# CaRe_Schematic_SMD_TOP_PANEL.net
KiCad netlist of a schematic drawn in Altium Designer
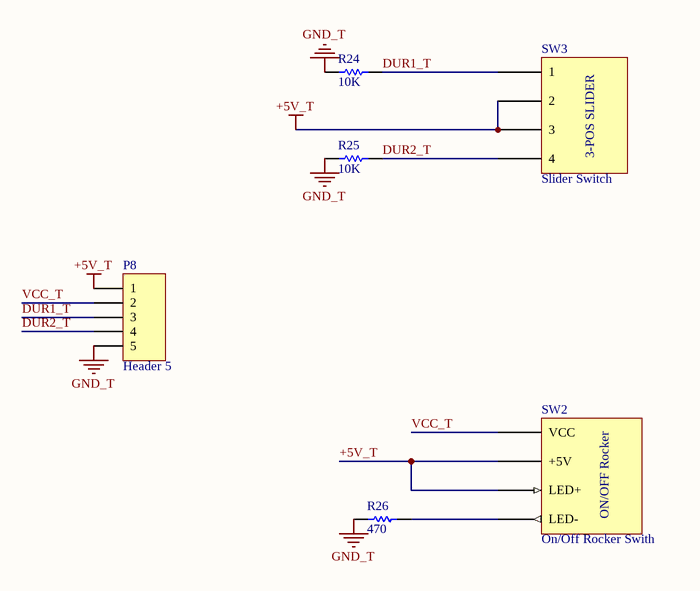
[diagram p0: CaRe_Schematic_SMD_TOP_PANEL.SchDoc]

(export (version "E")
  (design (tool "Eeschema 10.0.6"))
  (components
    (comp (ref "P8")
      (value "Header 5")
      (footprint "HDR1X5")
      (description "Header, 5-Pin")
      (fields (field (name "PUBLISHER") "Altium Limited"))
      (libsource (lib "CaRe_SchematicLib") (part "Header 5"))
    )
    (comp (ref "R24")
      (value "10K")
      (footprint "RES0805")
      (description "Resistor")
      (fields (field (name "PUBLISHER") "Altium Limited"))
      (libsource (lib "CaRe_SchematicLib") (part "Chip Res"))
    )
    (comp (ref "R25")
      (value "10K")
      (footprint "RES0805")
      (description "Resistor")
      (fields (field (name "PUBLISHER") "Altium Limited"))
      (libsource (lib "CaRe_SchematicLib") (part "Chip Res"))
    )
    (comp (ref "R26")
      (value "470")
      (footprint "RES0805")
      (description "Resistor")
      (fields (field (name "PUBLISHER") "Altium Limited"))
      (libsource (lib "CaRe_SchematicLib") (part "Chip Res"))
    )
    (comp (ref "SW2")
      (value "On/Off Rocker Swith")
      (footprint "Power_Switch")
      (libsource (lib "CaRe_SchematicLib") (part "ON/OFF Rocker"))
    )
    (comp (ref "SW3")
      (value "Slider Switch")
      (footprint "SLIDER")
      (libsource (lib "CaRe_SchematicLib") (part "SLIDER"))
    )
  )
  (nets
    (net (code "1") (name "+5V_T") (class "Default")
      (node (ref "P8") (pin "1") (pinfunction "1_1") (pintype "passive"))
      (node (ref "SW2") (pin "2") (pinfunction "+5V_2") (pintype "power_in"))
      (node (ref "SW2") (pin "3") (pinfunction "LED+_3") (pintype "input"))
      (node (ref "SW3") (pin "2") (pinfunction "2_2") (pintype "passive"))
      (node (ref "SW3") (pin "3") (pinfunction "3_3") (pintype "passive"))
    )
    (net (code "2") (name "/DUR1_T") (class "Default")
      (node (ref "P8") (pin "3") (pinfunction "3_3") (pintype "passive"))
      (node (ref "R24") (pin "2") (pinfunction "2_2") (pintype "passive"))
      (node (ref "SW3") (pin "1") (pinfunction "1_1") (pintype "passive"))
    )
    (net (code "3") (name "/DUR2_T") (class "Default")
      (node (ref "P8") (pin "4") (pinfunction "4_4") (pintype "passive"))
      (node (ref "R25") (pin "2") (pinfunction "2_2") (pintype "passive"))
      (node (ref "SW3") (pin "4") (pinfunction "4_4") (pintype "passive"))
    )
    (net (code "4") (name "/VCC_T") (class "Default")
      (node (ref "P8") (pin "2") (pinfunction "2_2") (pintype "passive"))
      (node (ref "SW2") (pin "1") (pinfunction "VCC_1") (pintype "power_in"))
    )
    (net (code "5") (name "GND_T") (class "Default")
      (node (ref "P8") (pin "5") (pinfunction "5_5") (pintype "passive"))
      (node (ref "R24") (pin "1") (pinfunction "1_1") (pintype "passive"))
      (node (ref "R25") (pin "1") (pinfunction "1_1") (pintype "passive"))
      (node (ref "R26") (pin "1") (pinfunction "1_1") (pintype "passive"))
    )
    (net (code "6") (name "Net-(SW2-LED-)") (class "Default")
      (node (ref "R26") (pin "2") (pinfunction "2_2") (pintype "passive"))
      (node (ref "SW2") (pin "4") (pinfunction "LED-_4") (pintype "output"))
    )
  )
)
